# FILTER.net
KiCad netlist of a schematic drawn in Altium Designer
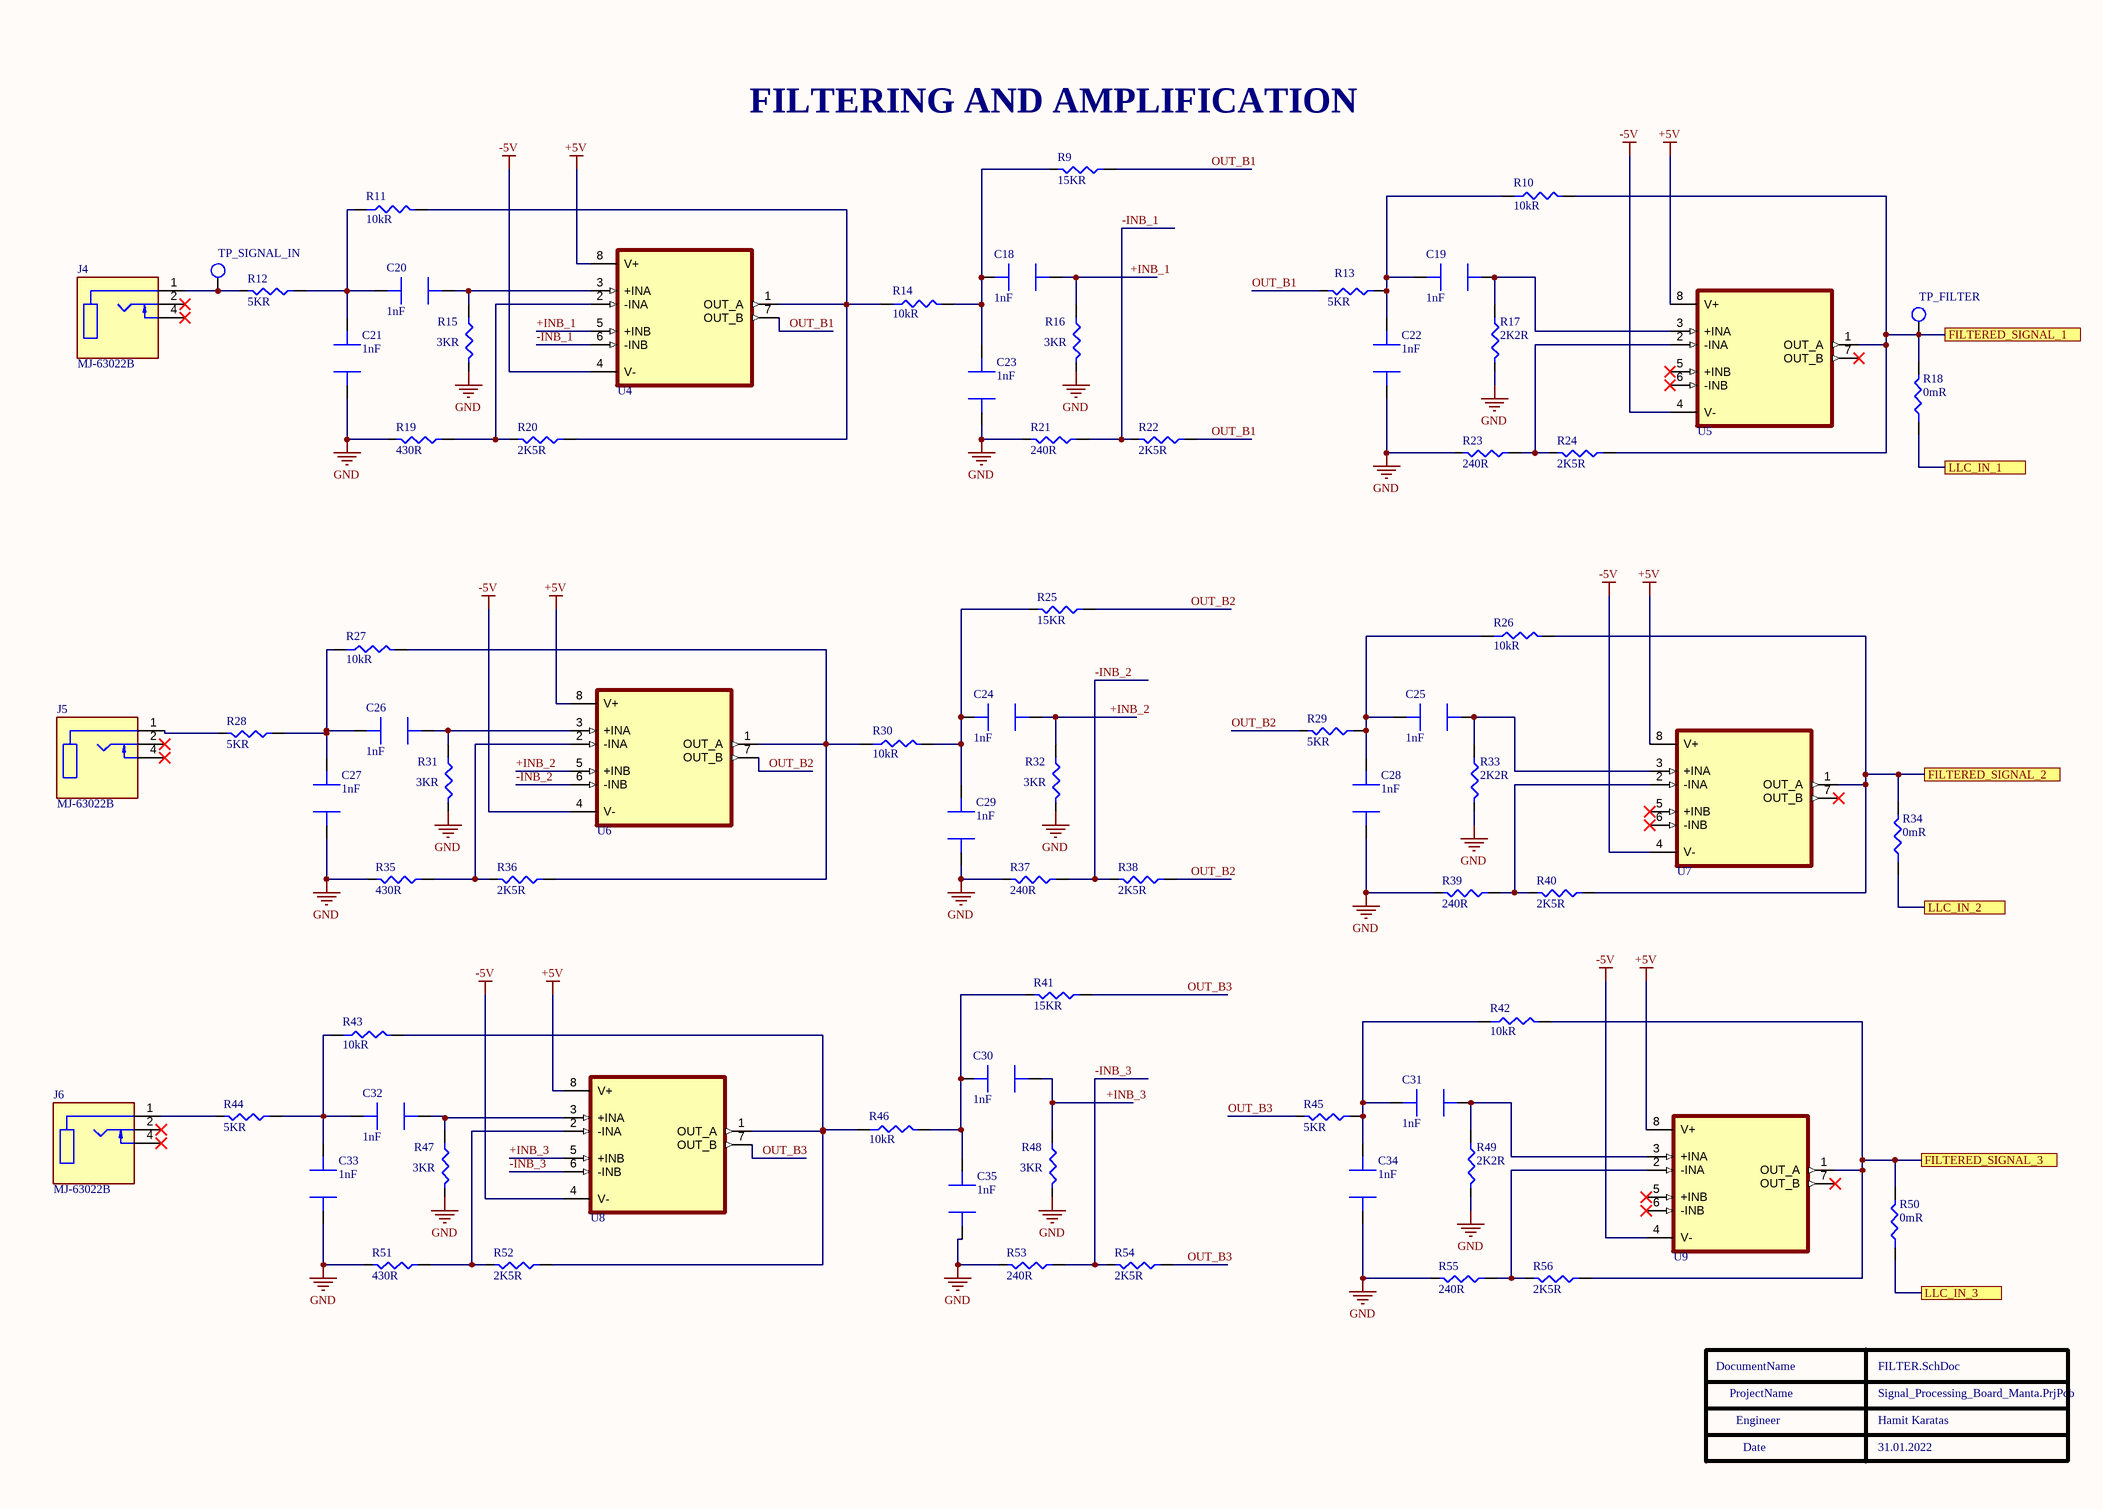
[diagram p0: FILTER.SchDoc]

(export (version "E")
  (design (tool "Eeschema 10.0.6"))
  (components
    (comp (ref "C18")
      (value "CAP CER 2.2uF")
      (footprint "CAP_1206")
      (description "Cap Ceramic 2.2uF 16V X7R 10% SMD 1206 125°C Plastic T/R")
      (fields
        (field (name "MANUFACTURER") "KEMET")
        (field (name "MANUFACTURER PART NUMBER") "C1206C225K4RACTU")
        (field (name "CAPACITANCE") "1nF")
      )
      (libsource (lib "altium_giris") (part "CAP CER 2.2uF"))
    )
    (comp (ref "C19")
      (value "CAP CER 2.2uF")
      (footprint "CAP_1206")
      (description "Cap Ceramic 2.2uF 16V X7R 10% SMD 1206 125°C Plastic T/R")
      (fields
        (field (name "MANUFACTURER") "KEMET")
        (field (name "MANUFACTURER PART NUMBER") "C1206C225K4RACTU")
        (field (name "CAPACITANCE") "1nF")
      )
      (libsource (lib "altium_giris") (part "CAP CER 2.2uF"))
    )
    (comp (ref "C20")
      (value "CAP CER 2.2uF")
      (footprint "CAP_1206")
      (description "Cap Ceramic 2.2uF 16V X7R 10% SMD 1206 125°C Plastic T/R")
      (fields
        (field (name "MANUFACTURER") "KEMET")
        (field (name "MANUFACTURER PART NUMBER") "C1206C225K4RACTU")
        (field (name "CAPACITANCE") "1nF")
      )
      (libsource (lib "altium_giris") (part "CAP CER 2.2uF"))
    )
    (comp (ref "C21")
      (value "CAP CER 2.2uF")
      (footprint "CAP_1206")
      (description "Cap Ceramic 2.2uF 16V X7R 10% SMD 1206 125°C Plastic T/R")
      (fields
        (field (name "MANUFACTURER") "KEMET")
        (field (name "MANUFACTURER PART NUMBER") "C1206C225K4RACTU")
        (field (name "CAPACITANCE") "1nF")
      )
      (libsource (lib "altium_giris") (part "CAP CER 2.2uF"))
    )
    (comp (ref "C22")
      (value "CAP CER 2.2uF")
      (footprint "CAP_1206")
      (description "Cap Ceramic 2.2uF 16V X7R 10% SMD 1206 125°C Plastic T/R")
      (fields
        (field (name "MANUFACTURER") "KEMET")
        (field (name "MANUFACTURER PART NUMBER") "C1206C225K4RACTU")
        (field (name "CAPACITANCE") "1nF")
      )
      (libsource (lib "altium_giris") (part "CAP CER 2.2uF"))
    )
    (comp (ref "C23")
      (value "CAP CER 2.2uF")
      (footprint "CAP_1206")
      (description "Cap Ceramic 2.2uF 16V X7R 10% SMD 1206 125°C Plastic T/R")
      (fields
        (field (name "MANUFACTURER") "KEMET")
        (field (name "MANUFACTURER PART NUMBER") "C1206C225K4RACTU")
        (field (name "CAPACITANCE") "1nF")
      )
      (libsource (lib "altium_giris") (part "CAP CER 2.2uF"))
    )
    (comp (ref "C24")
      (value "CAP CER 2.2uF")
      (footprint "CAP_1206")
      (description "Cap Ceramic 2.2uF 16V X7R 10% SMD 1206 125°C Plastic T/R")
      (fields
        (field (name "MANUFACTURER") "KEMET")
        (field (name "MANUFACTURER PART NUMBER") "C1206C225K4RACTU")
        (field (name "CAPACITANCE") "1nF")
      )
      (libsource (lib "altium_giris") (part "CAP CER 2.2uF"))
    )
    (comp (ref "C25")
      (value "CAP CER 2.2uF")
      (footprint "CAP_1206")
      (description "Cap Ceramic 2.2uF 16V X7R 10% SMD 1206 125°C Plastic T/R")
      (fields
        (field (name "MANUFACTURER") "KEMET")
        (field (name "MANUFACTURER PART NUMBER") "C1206C225K4RACTU")
        (field (name "CAPACITANCE") "1nF")
      )
      (libsource (lib "altium_giris") (part "CAP CER 2.2uF"))
    )
    (comp (ref "C26")
      (value "CAP CER 2.2uF")
      (footprint "CAP_1206")
      (description "Cap Ceramic 2.2uF 16V X7R 10% SMD 1206 125°C Plastic T/R")
      (fields
        (field (name "MANUFACTURER") "KEMET")
        (field (name "MANUFACTURER PART NUMBER") "C1206C225K4RACTU")
        (field (name "CAPACITANCE") "1nF")
      )
      (libsource (lib "altium_giris") (part "CAP CER 2.2uF"))
    )
    (comp (ref "C27")
      (value "CAP CER 2.2uF")
      (footprint "CAP_1206")
      (description "Cap Ceramic 2.2uF 16V X7R 10% SMD 1206 125°C Plastic T/R")
      (fields
        (field (name "MANUFACTURER") "KEMET")
        (field (name "MANUFACTURER PART NUMBER") "C1206C225K4RACTU")
        (field (name "CAPACITANCE") "1nF")
      )
      (libsource (lib "altium_giris") (part "CAP CER 2.2uF"))
    )
    (comp (ref "C28")
      (value "CAP CER 2.2uF")
      (footprint "CAP_1206")
      (description "Cap Ceramic 2.2uF 16V X7R 10% SMD 1206 125°C Plastic T/R")
      (fields
        (field (name "MANUFACTURER") "KEMET")
        (field (name "MANUFACTURER PART NUMBER") "C1206C225K4RACTU")
        (field (name "CAPACITANCE") "1nF")
      )
      (libsource (lib "altium_giris") (part "CAP CER 2.2uF"))
    )
    (comp (ref "C29")
      (value "CAP CER 2.2uF")
      (footprint "CAP_1206")
      (description "Cap Ceramic 2.2uF 16V X7R 10% SMD 1206 125°C Plastic T/R")
      (fields
        (field (name "MANUFACTURER") "KEMET")
        (field (name "MANUFACTURER PART NUMBER") "C1206C225K4RACTU")
        (field (name "CAPACITANCE") "1nF")
      )
      (libsource (lib "altium_giris") (part "CAP CER 2.2uF"))
    )
    (comp (ref "C30")
      (value "CAP CER 2.2uF")
      (footprint "CAP_1206")
      (description "Cap Ceramic 2.2uF 16V X7R 10% SMD 1206 125°C Plastic T/R")
      (fields
        (field (name "MANUFACTURER") "KEMET")
        (field (name "MANUFACTURER PART NUMBER") "C1206C225K4RACTU")
        (field (name "CAPACITANCE") "1nF")
      )
      (libsource (lib "altium_giris") (part "CAP CER 2.2uF"))
    )
    (comp (ref "C31")
      (value "CAP CER 2.2uF")
      (footprint "CAP_1206")
      (description "Cap Ceramic 2.2uF 16V X7R 10% SMD 1206 125°C Plastic T/R")
      (fields
        (field (name "MANUFACTURER") "KEMET")
        (field (name "MANUFACTURER PART NUMBER") "C1206C225K4RACTU")
        (field (name "CAPACITANCE") "1nF")
      )
      (libsource (lib "altium_giris") (part "CAP CER 2.2uF"))
    )
    (comp (ref "C32")
      (value "CAP CER 2.2uF")
      (footprint "CAP_1206")
      (description "Cap Ceramic 2.2uF 16V X7R 10% SMD 1206 125°C Plastic T/R")
      (fields
        (field (name "MANUFACTURER") "KEMET")
        (field (name "MANUFACTURER PART NUMBER") "C1206C225K4RACTU")
        (field (name "CAPACITANCE") "1nF")
      )
      (libsource (lib "altium_giris") (part "CAP CER 2.2uF"))
    )
    (comp (ref "C33")
      (value "CAP CER 2.2uF")
      (footprint "CAP_1206")
      (description "Cap Ceramic 2.2uF 16V X7R 10% SMD 1206 125°C Plastic T/R")
      (fields
        (field (name "MANUFACTURER") "KEMET")
        (field (name "MANUFACTURER PART NUMBER") "C1206C225K4RACTU")
        (field (name "CAPACITANCE") "1nF")
      )
      (libsource (lib "altium_giris") (part "CAP CER 2.2uF"))
    )
    (comp (ref "C34")
      (value "CAP CER 2.2uF")
      (footprint "CAP_1206")
      (description "Cap Ceramic 2.2uF 16V X7R 10% SMD 1206 125°C Plastic T/R")
      (fields
        (field (name "MANUFACTURER") "KEMET")
        (field (name "MANUFACTURER PART NUMBER") "C1206C225K4RACTU")
        (field (name "CAPACITANCE") "1nF")
      )
      (libsource (lib "altium_giris") (part "CAP CER 2.2uF"))
    )
    (comp (ref "C35")
      (value "CAP CER 2.2uF")
      (footprint "CAP_1206")
      (description "Cap Ceramic 2.2uF 16V X7R 10% SMD 1206 125°C Plastic T/R")
      (fields
        (field (name "MANUFACTURER") "KEMET")
        (field (name "MANUFACTURER PART NUMBER") "C1206C225K4RACTU")
        (field (name "CAPACITANCE") "1nF")
      )
      (libsource (lib "altium_giris") (part "CAP CER 2.2uF"))
    )
    (comp (ref "J4")
      (value "MJ-63022B")
      (footprint "JACK FEMALE 6.3")
      (description "Conn Audio Jack F 2 POS Solder RA Thru-Hole 3 Terminal 1 Port Bulk")
      (fields (field (name "MANUFACTURER") "CUI Devices"))
      (libsource (lib "altium_giris") (part "MJ-63022B"))
    )
    (comp (ref "J5")
      (value "MJ-63022B")
      (footprint "JACK FEMALE 6.3")
      (description "Conn Audio Jack F 2 POS Solder RA Thru-Hole 3 Terminal 1 Port Bulk")
      (fields (field (name "MANUFACTURER") "CUI Devices"))
      (libsource (lib "altium_giris") (part "MJ-63022B"))
    )
    (comp (ref "J6")
      (value "MJ-63022B")
      (footprint "JACK FEMALE 6.3")
      (description "Conn Audio Jack F 2 POS Solder RA Thru-Hole 3 Terminal 1 Port Bulk")
      (fields (field (name "MANUFACTURER") "CUI Devices"))
      (libsource (lib "altium_giris") (part "MJ-63022B"))
    )
    (comp (ref "R9")
      (value "RC0603FR-0710KL")
      (footprint "RES_0603")
      (description "RES 1K %1 OHM 0603 SMD")
      (fields
        (field (name "MANUFACTURER") "Yageo")
        (field (name "MANUFACTURER PART NUMBER") "RC0603JR-071KL")
        (field (name "RESISTANCE") "15KR")
        (field (name "DESIGNED BY") "Hamit")
      )
      (libsource (lib "altium_giris") (part "RES 1K OHM 0603"))
    )
    (comp (ref "R10")
      (value "RES 10K OHM 0603")
      (footprint "RES_0603")
      (description "Res General Purpose Thick Film 0603 10K Ohm 1% 1/10W ±100ppm/°C Molded SMD Paper T/R")
      (fields
        (field (name "MANUFACTURER") "Yageo")
        (field (name "MANUFACTURER PART NUMBER") "RC0603FR-0710KL")
        (field (name "RESISTANCE") "10kR")
        (field (name "DESIGNED BY") "Hamit")
      )
      (libsource (lib "altium_giris") (part "RES 10K OHM 0603"))
    )
    (comp (ref "R11")
      (value "RES 10K OHM 0603")
      (footprint "RES_0603")
      (description "Res General Purpose Thick Film 0603 10K Ohm 1% 1/10W ±100ppm/°C Molded SMD Paper T/R")
      (fields
        (field (name "MANUFACTURER") "Yageo")
        (field (name "MANUFACTURER PART NUMBER") "RC0603FR-0710KL")
        (field (name "RESISTANCE") "10kR")
        (field (name "DESIGNED BY") "Hamit")
      )
      (libsource (lib "altium_giris") (part "RES 10K OHM 0603"))
    )
    (comp (ref "R12")
      (value "RC0603FR-0710KL")
      (footprint "RES_0603")
      (description "RES 1K %1 OHM 0603 SMD")
      (fields
        (field (name "MANUFACTURER") "Yageo")
        (field (name "MANUFACTURER PART NUMBER") "RC0603JR-071KL")
        (field (name "RESISTANCE") "5KR")
        (field (name "DESIGNED BY") "Hamit")
      )
      (libsource (lib "altium_giris") (part "RES 1K OHM 0603"))
    )
    (comp (ref "R13")
      (value "RC0603FR-0710KL")
      (footprint "RES_0603")
      (description "RES 1K %1 OHM 0603 SMD")
      (fields
        (field (name "MANUFACTURER") "Yageo")
        (field (name "MANUFACTURER PART NUMBER") "RC0603JR-071KL")
        (field (name "RESISTANCE") "5KR")
        (field (name "DESIGNED BY") "Hamit")
      )
      (libsource (lib "altium_giris") (part "RES 1K OHM 0603"))
    )
    (comp (ref "R14")
      (value "RES 10K OHM 0603")
      (footprint "RES_0603")
      (description "Res General Purpose Thick Film 0603 10K Ohm 1% 1/10W ±100ppm/°C Molded SMD Paper T/R")
      (fields
        (field (name "MANUFACTURER") "Yageo")
        (field (name "MANUFACTURER PART NUMBER") "RC0603FR-0710KL")
        (field (name "RESISTANCE") "10kR")
        (field (name "DESIGNED BY") "Hamit")
      )
      (libsource (lib "altium_giris") (part "RES 10K OHM 0603"))
    )
    (comp (ref "R15")
      (value "430R")
      (footprint "RES 0805")
      (description "Res Thick Film 0805 430 Ohm 1% 1/8W ±100ppm/°C Molded SMD SMD Paper T/R")
      (fields
        (field (name "MANUFACTURER") "Stackpole Electronics")
        (field (name "MANUFACTURER PART NUMBER") "RMCF0805FT430R")
        (field (name "RESISTANCE") "3KR")
      )
      (libsource (lib "altium_giris") (part "RES 430 OHM 0805"))
    )
    (comp (ref "R16")
      (value "430R")
      (footprint "RES 0805")
      (description "Res Thick Film 0805 430 Ohm 1% 1/8W ±100ppm/°C Molded SMD SMD Paper T/R")
      (fields
        (field (name "MANUFACTURER") "Stackpole Electronics")
        (field (name "MANUFACTURER PART NUMBER") "RMCF0805FT430R")
        (field (name "RESISTANCE") "3KR")
      )
      (libsource (lib "altium_giris") (part "RES 430 OHM 0805"))
    )
    (comp (ref "R17")
      (value "RC0603FR-0710KL")
      (footprint "RES_0603")
      (description "RES 1K %1 OHM 0603 SMD")
      (fields
        (field (name "MANUFACTURER") "Yageo")
        (field (name "MANUFACTURER PART NUMBER") "RC0603JR-071KL")
        (field (name "RESISTANCE") "2K2R")
        (field (name "DESIGNED BY") "Hamit")
      )
      (libsource (lib "altium_giris") (part "RES 1K OHM 0603"))
    )
    (comp (ref "R18")
      (value "RC0603JR-070RL")
      (footprint "RES_0603")
      (description "RES SMD 0 OHM JUMPER 1/10W 0603")
      (fields
        (field (name "MANUFACTURER") "Yageo")
        (field (name "TOLERANCE") "1%")
        (field (name "RESISTANCE") "0mR")
        (field (name "DESIGNED BY") "Hamit")
      )
      (libsource (lib "altium_giris") (part "RES 0 ohm 0603"))
    )
    (comp (ref "R19")
      (value "430R")
      (footprint "RES 0805")
      (description "Res Thick Film 0805 430 Ohm 1% 1/8W ±100ppm/°C Molded SMD SMD Paper T/R")
      (fields
        (field (name "MANUFACTURER") "Stackpole Electronics")
        (field (name "MANUFACTURER PART NUMBER") "RMCF0805FT430R")
        (field (name "RESISTANCE") "430R")
      )
      (libsource (lib "altium_giris") (part "RES 430 OHM 0805"))
    )
    (comp (ref "R20")
      (value "RC0603FR-0710KL")
      (footprint "RES_0603")
      (description "RES 1K %1 OHM 0603 SMD")
      (fields
        (field (name "MANUFACTURER") "Yageo")
        (field (name "MANUFACTURER PART NUMBER") "RC0603JR-071KL")
        (field (name "RESISTANCE") "2K5R")
        (field (name "DESIGNED BY") "Hamit")
      )
      (libsource (lib "altium_giris") (part "RES 1K OHM 0603"))
    )
    (comp (ref "R21")
      (value "430R")
      (footprint "RES 0805")
      (description "Res Thick Film 0805 430 Ohm 1% 1/8W ±100ppm/°C Molded SMD SMD Paper T/R")
      (fields
        (field (name "MANUFACTURER") "Stackpole Electronics")
        (field (name "MANUFACTURER PART NUMBER") "RMCF0805FT430R")
        (field (name "RESISTANCE") "240R")
      )
      (libsource (lib "altium_giris") (part "RES 430 OHM 0805"))
    )
    (comp (ref "R22")
      (value "RC0603FR-0710KL")
      (footprint "RES_0603")
      (description "RES 1K %1 OHM 0603 SMD")
      (fields
        (field (name "MANUFACTURER") "Yageo")
        (field (name "MANUFACTURER PART NUMBER") "RC0603JR-071KL")
        (field (name "RESISTANCE") "2K5R")
        (field (name "DESIGNED BY") "Hamit")
      )
      (libsource (lib "altium_giris") (part "RES 1K OHM 0603"))
    )
    (comp (ref "R23")
      (value "430R")
      (footprint "RES 0805")
      (description "Res Thick Film 0805 430 Ohm 1% 1/8W ±100ppm/°C Molded SMD SMD Paper T/R")
      (fields
        (field (name "MANUFACTURER") "Stackpole Electronics")
        (field (name "MANUFACTURER PART NUMBER") "RMCF0805FT430R")
        (field (name "RESISTANCE") "240R")
      )
      (libsource (lib "altium_giris") (part "RES 430 OHM 0805"))
    )
    (comp (ref "R24")
      (value "RC0603FR-0710KL")
      (footprint "RES_0603")
      (description "RES 1K %1 OHM 0603 SMD")
      (fields
        (field (name "MANUFACTURER") "Yageo")
        (field (name "MANUFACTURER PART NUMBER") "RC0603JR-071KL")
        (field (name "RESISTANCE") "2K5R")
        (field (name "DESIGNED BY") "Hamit")
      )
      (libsource (lib "altium_giris") (part "RES 1K OHM 0603"))
    )
    (comp (ref "R25")
      (value "RC0603FR-0710KL")
      (footprint "RES_0603")
      (description "RES 1K %1 OHM 0603 SMD")
      (fields
        (field (name "MANUFACTURER") "Yageo")
        (field (name "MANUFACTURER PART NUMBER") "RC0603JR-071KL")
        (field (name "RESISTANCE") "15KR")
        (field (name "DESIGNED BY") "Hamit")
      )
      (libsource (lib "altium_giris") (part "RES 1K OHM 0603"))
    )
    (comp (ref "R26")
      (value "RES 10K OHM 0603")
      (footprint "RES_0603")
      (description "Res General Purpose Thick Film 0603 10K Ohm 1% 1/10W ±100ppm/°C Molded SMD Paper T/R")
      (fields
        (field (name "MANUFACTURER") "Yageo")
        (field (name "MANUFACTURER PART NUMBER") "RC0603FR-0710KL")
        (field (name "RESISTANCE") "10kR")
        (field (name "DESIGNED BY") "Hamit")
      )
      (libsource (lib "altium_giris") (part "RES 10K OHM 0603"))
    )
    (comp (ref "R27")
      (value "RES 10K OHM 0603")
      (footprint "RES_0603")
      (description "Res General Purpose Thick Film 0603 10K Ohm 1% 1/10W ±100ppm/°C Molded SMD Paper T/R")
      (fields
        (field (name "MANUFACTURER") "Yageo")
        (field (name "MANUFACTURER PART NUMBER") "RC0603FR-0710KL")
        (field (name "RESISTANCE") "10kR")
        (field (name "DESIGNED BY") "Hamit")
      )
      (libsource (lib "altium_giris") (part "RES 10K OHM 0603"))
    )
    (comp (ref "R28")
      (value "RC0603FR-0710KL")
      (footprint "RES_0603")
      (description "RES 1K %1 OHM 0603 SMD")
      (fields
        (field (name "MANUFACTURER") "Yageo")
        (field (name "MANUFACTURER PART NUMBER") "RC0603JR-071KL")
        (field (name "RESISTANCE") "5KR")
        (field (name "DESIGNED BY") "Hamit")
      )
      (libsource (lib "altium_giris") (part "RES 1K OHM 0603"))
    )
    (comp (ref "R29")
      (value "RC0603FR-0710KL")
      (footprint "RES_0603")
      (description "RES 1K %1 OHM 0603 SMD")
      (fields
        (field (name "MANUFACTURER") "Yageo")
        (field (name "MANUFACTURER PART NUMBER") "RC0603JR-071KL")
        (field (name "RESISTANCE") "5KR")
        (field (name "DESIGNED BY") "Hamit")
      )
      (libsource (lib "altium_giris") (part "RES 1K OHM 0603"))
    )
    (comp (ref "R30")
      (value "RES 10K OHM 0603")
      (footprint "RES_0603")
      (description "Res General Purpose Thick Film 0603 10K Ohm 1% 1/10W ±100ppm/°C Molded SMD Paper T/R")
      (fields
        (field (name "MANUFACTURER") "Yageo")
        (field (name "MANUFACTURER PART NUMBER") "RC0603FR-0710KL")
        (field (name "RESISTANCE") "10kR")
        (field (name "DESIGNED BY") "Hamit")
      )
      (libsource (lib "altium_giris") (part "RES 10K OHM 0603"))
    )
    (comp (ref "R31")
      (value "430R")
      (footprint "RES 0805")
      (description "Res Thick Film 0805 430 Ohm 1% 1/8W ±100ppm/°C Molded SMD SMD Paper T/R")
      (fields
        (field (name "MANUFACTURER") "Stackpole Electronics")
        (field (name "MANUFACTURER PART NUMBER") "RMCF0805FT430R")
        (field (name "RESISTANCE") "3KR")
      )
      (libsource (lib "altium_giris") (part "RES 430 OHM 0805"))
    )
    (comp (ref "R32")
      (value "430R")
      (footprint "RES 0805")
      (description "Res Thick Film 0805 430 Ohm 1% 1/8W ±100ppm/°C Molded SMD SMD Paper T/R")
      (fields
        (field (name "MANUFACTURER") "Stackpole Electronics")
        (field (name "MANUFACTURER PART NUMBER") "RMCF0805FT430R")
        (field (name "RESISTANCE") "3KR")
      )
      (libsource (lib "altium_giris") (part "RES 430 OHM 0805"))
    )
    (comp (ref "R33")
      (value "RC0603FR-0710KL")
      (footprint "RES_0603")
      (description "RES 1K %1 OHM 0603 SMD")
      (fields
        (field (name "MANUFACTURER") "Yageo")
        (field (name "MANUFACTURER PART NUMBER") "RC0603JR-071KL")
        (field (name "RESISTANCE") "2K2R")
        (field (name "DESIGNED BY") "Hamit")
      )
      (libsource (lib "altium_giris") (part "RES 1K OHM 0603"))
    )
    (comp (ref "R34")
      (value "RC0603JR-070RL")
      (footprint "RES_0603")
      (description "RES SMD 0 OHM JUMPER 1/10W 0603")
      (fields
        (field (name "MANUFACTURER") "Yageo")
        (field (name "TOLERANCE") "1%")
        (field (name "RESISTANCE") "0mR")
        (field (name "DESIGNED BY") "Hamit")
      )
      (libsource (lib "altium_giris") (part "RES 0 ohm 0603"))
    )
    (comp (ref "R35")
      (value "430R")
      (footprint "RES 0805")
      (description "Res Thick Film 0805 430 Ohm 1% 1/8W ±100ppm/°C Molded SMD SMD Paper T/R")
      (fields
        (field (name "MANUFACTURER") "Stackpole Electronics")
        (field (name "MANUFACTURER PART NUMBER") "RMCF0805FT430R")
        (field (name "RESISTANCE") "430R")
      )
      (libsource (lib "altium_giris") (part "RES 430 OHM 0805"))
    )
    (comp (ref "R36")
      (value "RC0603FR-0710KL")
      (footprint "RES_0603")
      (description "RES 1K %1 OHM 0603 SMD")
      (fields
        (field (name "MANUFACTURER") "Yageo")
        (field (name "MANUFACTURER PART NUMBER") "RC0603JR-071KL")
        (field (name "RESISTANCE") "2K5R")
        (field (name "DESIGNED BY") "Hamit")
      )
      (libsource (lib "altium_giris") (part "RES 1K OHM 0603"))
    )
    (comp (ref "R37")
      (value "430R")
      (footprint "RES 0805")
      (description "Res Thick Film 0805 430 Ohm 1% 1/8W ±100ppm/°C Molded SMD SMD Paper T/R")
      (fields
        (field (name "MANUFACTURER") "Stackpole Electronics")
        (field (name "MANUFACTURER PART NUMBER") "RMCF0805FT430R")
        (field (name "RESISTANCE") "240R")
      )
      (libsource (lib "altium_giris") (part "RES 430 OHM 0805"))
    )
    (comp (ref "R38")
      (value "RC0603FR-0710KL")
      (footprint "RES_0603")
      (description "RES 1K %1 OHM 0603 SMD")
      (fields
        (field (name "MANUFACTURER") "Yageo")
        (field (name "MANUFACTURER PART NUMBER") "RC0603JR-071KL")
        (field (name "RESISTANCE") "2K5R")
        (field (name "DESIGNED BY") "Hamit")
      )
      (libsource (lib "altium_giris") (part "RES 1K OHM 0603"))
    )
    (comp (ref "R39")
      (value "430R")
      (footprint "RES 0805")
      (description "Res Thick Film 0805 430 Ohm 1% 1/8W ±100ppm/°C Molded SMD SMD Paper T/R")
      (fields
        (field (name "MANUFACTURER") "Stackpole Electronics")
        (field (name "MANUFACTURER PART NUMBER") "RMCF0805FT430R")
        (field (name "RESISTANCE") "240R")
      )
      (libsource (lib "altium_giris") (part "RES 430 OHM 0805"))
    )
    (comp (ref "R40")
      (value "RC0603FR-0710KL")
      (footprint "RES_0603")
      (description "RES 1K %1 OHM 0603 SMD")
      (fields
        (field (name "MANUFACTURER") "Yageo")
        (field (name "MANUFACTURER PART NUMBER") "RC0603JR-071KL")
        (field (name "RESISTANCE") "2K5R")
        (field (name "DESIGNED BY") "Hamit")
      )
      (libsource (lib "altium_giris") (part "RES 1K OHM 0603"))
    )
    (comp (ref "R41")
      (value "RC0603FR-0710KL")
      (footprint "RES_0603")
      (description "RES 1K %1 OHM 0603 SMD")
      (fields
        (field (name "MANUFACTURER") "Yageo")
        (field (name "MANUFACTURER PART NUMBER") "RC0603JR-071KL")
        (field (name "RESISTANCE") "15KR")
        (field (name "DESIGNED BY") "Hamit")
      )
      (libsource (lib "altium_giris") (part "RES 1K OHM 0603"))
    )
    (comp (ref "R42")
      (value "RES 10K OHM 0603")
      (footprint "RES_0603")
      (description "Res General Purpose Thick Film 0603 10K Ohm 1% 1/10W ±100ppm/°C Molded SMD Paper T/R")
      (fields
        (field (name "MANUFACTURER") "Yageo")
        (field (name "MANUFACTURER PART NUMBER") "RC0603FR-0710KL")
        (field (name "RESISTANCE") "10kR")
        (field (name "DESIGNED BY") "Hamit")
      )
      (libsource (lib "altium_giris") (part "RES 10K OHM 0603"))
    )
    (comp (ref "R43")
      (value "RES 10K OHM 0603")
      (footprint "RES_0603")
      (description "Res General Purpose Thick Film 0603 10K Ohm 1% 1/10W ±100ppm/°C Molded SMD Paper T/R")
      (fields
        (field (name "MANUFACTURER") "Yageo")
        (field (name "MANUFACTURER PART NUMBER") "RC0603FR-0710KL")
        (field (name "RESISTANCE") "10kR")
        (field (name "DESIGNED BY") "Hamit")
      )
      (libsource (lib "altium_giris") (part "RES 10K OHM 0603"))
    )
    (comp (ref "R44")
      (value "RC0603FR-0710KL")
      (footprint "RES_0603")
      (description "RES 1K %1 OHM 0603 SMD")
      (fields
        (field (name "MANUFACTURER") "Yageo")
        (field (name "MANUFACTURER PART NUMBER") "RC0603JR-071KL")
        (field (name "RESISTANCE") "5KR")
        (field (name "DESIGNED BY") "Hamit")
      )
      (libsource (lib "altium_giris") (part "RES 1K OHM 0603"))
    )
    (comp (ref "R45")
      (value "RC0603FR-0710KL")
      (footprint "RES_0603")
      (description "RES 1K %1 OHM 0603 SMD")
      (fields
        (field (name "MANUFACTURER") "Yageo")
        (field (name "MANUFACTURER PART NUMBER") "RC0603JR-071KL")
        (field (name "RESISTANCE") "5KR")
        (field (name "DESIGNED BY") "Hamit")
      )
      (libsource (lib "altium_giris") (part "RES 1K OHM 0603"))
    )
    (comp (ref "R46")
      (value "RES 10K OHM 0603")
      (footprint "RES_0603")
      (description "Res General Purpose Thick Film 0603 10K Ohm 1% 1/10W ±100ppm/°C Molded SMD Paper T/R")
      (fields
        (field (name "MANUFACTURER") "Yageo")
        (field (name "MANUFACTURER PART NUMBER") "RC0603FR-0710KL")
        (field (name "RESISTANCE") "10kR")
        (field (name "DESIGNED BY") "Hamit")
      )
      (libsource (lib "altium_giris") (part "RES 10K OHM 0603"))
    )
    (comp (ref "R47")
      (value "430R")
      (footprint "RES 0805")
      (description "Res Thick Film 0805 430 Ohm 1% 1/8W ±100ppm/°C Molded SMD SMD Paper T/R")
      (fields
        (field (name "MANUFACTURER") "Stackpole Electronics")
        (field (name "MANUFACTURER PART NUMBER") "RMCF0805FT430R")
        (field (name "RESISTANCE") "3KR")
      )
      (libsource (lib "altium_giris") (part "RES 430 OHM 0805"))
    )
    (comp (ref "R48")
      (value "430R")
      (footprint "RES 0805")
      (description "Res Thick Film 0805 430 Ohm 1% 1/8W ±100ppm/°C Molded SMD SMD Paper T/R")
      (fields
        (field (name "MANUFACTURER") "Stackpole Electronics")
        (field (name "MANUFACTURER PART NUMBER") "RMCF0805FT430R")
        (field (name "RESISTANCE") "3KR")
      )
      (libsource (lib "altium_giris") (part "RES 430 OHM 0805"))
    )
    (comp (ref "R49")
      (value "RC0603FR-0710KL")
      (footprint "RES_0603")
      (description "RES 1K %1 OHM 0603 SMD")
      (fields
        (field (name "MANUFACTURER") "Yageo")
        (field (name "MANUFACTURER PART NUMBER") "RC0603JR-071KL")
        (field (name "RESISTANCE") "2K2R")
        (field (name "DESIGNED BY") "Hamit")
      )
      (libsource (lib "altium_giris") (part "RES 1K OHM 0603"))
    )
    (comp (ref "R50")
      (value "RC0603JR-070RL")
      (footprint "RES_0603")
      (description "RES SMD 0 OHM JUMPER 1/10W 0603")
      (fields
        (field (name "MANUFACTURER") "Yageo")
        (field (name "TOLERANCE") "1%")
        (field (name "RESISTANCE") "0mR")
        (field (name "DESIGNED BY") "Hamit")
      )
      (libsource (lib "altium_giris") (part "RES 0 ohm 0603"))
    )
    (comp (ref "R51")
      (value "430R")
      (footprint "RES 0805")
      (description "Res Thick Film 0805 430 Ohm 1% 1/8W ±100ppm/°C Molded SMD SMD Paper T/R")
      (fields
        (field (name "MANUFACTURER") "Stackpole Electronics")
        (field (name "MANUFACTURER PART NUMBER") "RMCF0805FT430R")
        (field (name "RESISTANCE") "430R")
      )
      (libsource (lib "altium_giris") (part "RES 430 OHM 0805"))
    )
    (comp (ref "R52")
      (value "RC0603FR-0710KL")
      (footprint "RES_0603")
      (description "RES 1K %1 OHM 0603 SMD")
      (fields
        (field (name "MANUFACTURER") "Yageo")
        (field (name "MANUFACTURER PART NUMBER") "RC0603JR-071KL")
        (field (name "RESISTANCE") "2K5R")
        (field (name "DESIGNED BY") "Hamit")
      )
      (libsource (lib "altium_giris") (part "RES 1K OHM 0603"))
    )
    (comp (ref "R53")
      (value "430R")
      (footprint "RES 0805")
      (description "Res Thick Film 0805 430 Ohm 1% 1/8W ±100ppm/°C Molded SMD SMD Paper T/R")
      (fields
        (field (name "MANUFACTURER") "Stackpole Electronics")
        (field (name "MANUFACTURER PART NUMBER") "RMCF0805FT430R")
        (field (name "RESISTANCE") "240R")
      )
      (libsource (lib "altium_giris") (part "RES 430 OHM 0805"))
    )
    (comp (ref "R54")
      (value "RC0603FR-0710KL")
      (footprint "RES_0603")
      (description "RES 1K %1 OHM 0603 SMD")
      (fields
        (field (name "MANUFACTURER") "Yageo")
        (field (name "MANUFACTURER PART NUMBER") "RC0603JR-071KL")
        (field (name "RESISTANCE") "2K5R")
        (field (name "DESIGNED BY") "Hamit")
      )
      (libsource (lib "altium_giris") (part "RES 1K OHM 0603"))
    )
    (comp (ref "R55")
      (value "430R")
      (footprint "RES 0805")
      (description "Res Thick Film 0805 430 Ohm 1% 1/8W ±100ppm/°C Molded SMD SMD Paper T/R")
      (fields
        (field (name "MANUFACTURER") "Stackpole Electronics")
        (field (name "MANUFACTURER PART NUMBER") "RMCF0805FT430R")
        (field (name "RESISTANCE") "240R")
      )
      (libsource (lib "altium_giris") (part "RES 430 OHM 0805"))
    )
    (comp (ref "R56")
      (value "RC0603FR-0710KL")
      (footprint "RES_0603")
      (description "RES 1K %1 OHM 0603 SMD")
      (fields
        (field (name "MANUFACTURER") "Yageo")
        (field (name "MANUFACTURER PART NUMBER") "RC0603JR-071KL")
        (field (name "RESISTANCE") "2K5R")
        (field (name "DESIGNED BY") "Hamit")
      )
      (libsource (lib "altium_giris") (part "RES 1K OHM 0603"))
    )
    (comp (ref "TP_FILTER")
      (value "TEST_POINT")
      (footprint "TEST POINT")
      (libsource (lib "altium_giris") (part "TEST POINT"))
    )
    (comp (ref "TP_SIGNAL_IN")
      (value "TEST_POINT")
      (footprint "TEST POINT")
      (libsource (lib "altium_giris") (part "TEST POINT"))
    )
    (comp (ref "U4")
      (value "Opamp lmh6612")
      (footprint "SOIC-8")
      (description "Single Supply, Dual 345 MHz Rail-to-Rail Output Amplifier and PLC Line Driver 8-SOIC -40 to 125")
      (fields
        (field (name "MANUFACTURER") "TI National Semiconductor")
        (field (name "MANUFACTURER PART NUMBER") "LMH6612MAX/NOPB")
      )
      (libsource (lib "altium_giris") (part "Opamp lmh6612"))
    )
    (comp (ref "U5")
      (value "Opamp lmh6612")
      (footprint "SOIC-8")
      (description "Single Supply, Dual 345 MHz Rail-to-Rail Output Amplifier and PLC Line Driver 8-SOIC -40 to 125")
      (fields
        (field (name "MANUFACTURER") "TI National Semiconductor")
        (field (name "MANUFACTURER PART NUMBER") "LMH6612MAX/NOPB")
      )
      (libsource (lib "altium_giris") (part "Opamp lmh6612"))
    )
    (comp (ref "U6")
      (value "Opamp lmh6612")
      (footprint "SOIC-8")
      (description "Single Supply, Dual 345 MHz Rail-to-Rail Output Amplifier and PLC Line Driver 8-SOIC -40 to 125")
      (fields
        (field (name "MANUFACTURER") "TI National Semiconductor")
        (field (name "MANUFACTURER PART NUMBER") "LMH6612MAX/NOPB")
      )
      (libsource (lib "altium_giris") (part "Opamp lmh6612"))
    )
    (comp (ref "U7")
      (value "Opamp lmh6612")
      (footprint "SOIC-8")
      (description "Single Supply, Dual 345 MHz Rail-to-Rail Output Amplifier and PLC Line Driver 8-SOIC -40 to 125")
      (fields
        (field (name "MANUFACTURER") "TI National Semiconductor")
        (field (name "MANUFACTURER PART NUMBER") "LMH6612MAX/NOPB")
      )
      (libsource (lib "altium_giris") (part "Opamp lmh6612"))
    )
    (comp (ref "U8")
      (value "Opamp lmh6612")
      (footprint "SOIC-8")
      (description "Single Supply, Dual 345 MHz Rail-to-Rail Output Amplifier and PLC Line Driver 8-SOIC -40 to 125")
      (fields
        (field (name "MANUFACTURER") "TI National Semiconductor")
        (field (name "MANUFACTURER PART NUMBER") "LMH6612MAX/NOPB")
      )
      (libsource (lib "altium_giris") (part "Opamp lmh6612"))
    )
    (comp (ref "U9")
      (value "Opamp lmh6612")
      (footprint "SOIC-8")
      (description "Single Supply, Dual 345 MHz Rail-to-Rail Output Amplifier and PLC Line Driver 8-SOIC -40 to 125")
      (fields
        (field (name "MANUFACTURER") "TI National Semiconductor")
        (field (name "MANUFACTURER PART NUMBER") "LMH6612MAX/NOPB")
      )
      (libsource (lib "altium_giris") (part "Opamp lmh6612"))
    )
  )
  (nets
    (net (code "1") (name "+5V") (class "Default")
      (node (ref "U4") (pin "8") (pinfunction "V+_8") (pintype "power_in"))
      (node (ref "U5") (pin "8") (pinfunction "V+_8") (pintype "power_in"))
      (node (ref "U6") (pin "8") (pinfunction "V+_8") (pintype "power_in"))
      (node (ref "U7") (pin "8") (pinfunction "V+_8") (pintype "power_in"))
      (node (ref "U8") (pin "8") (pinfunction "V+_8") (pintype "power_in"))
      (node (ref "U9") (pin "8") (pinfunction "V+_8") (pintype "power_in"))
    )
    (net (code "2") (name "-5V") (class "Default")
      (node (ref "U4") (pin "4") (pinfunction "V-_4") (pintype "power_in"))
      (node (ref "U5") (pin "4") (pinfunction "V-_4") (pintype "power_in"))
      (node (ref "U6") (pin "4") (pinfunction "V-_4") (pintype "power_in"))
      (node (ref "U7") (pin "4") (pinfunction "V-_4") (pintype "power_in"))
      (node (ref "U8") (pin "4") (pinfunction "V-_4") (pintype "power_in"))
      (node (ref "U9") (pin "4") (pinfunction "V-_4") (pintype "power_in"))
    )
    (net (code "3") (name "/+INB_1") (class "Default")
      (node (ref "C18") (pin "2") (pinfunction "2_2") (pintype "passive"))
      (node (ref "R16") (pin "2") (pinfunction "2_2") (pintype "passive"))
      (node (ref "U4") (pin "5") (pinfunction "+INB_5") (pintype "input"))
    )
    (net (code "4") (name "/+INB_2") (class "Default")
      (node (ref "C24") (pin "2") (pinfunction "2_2") (pintype "passive"))
      (node (ref "R32") (pin "2") (pinfunction "2_2") (pintype "passive"))
      (node (ref "U6") (pin "5") (pinfunction "+INB_5") (pintype "input"))
    )
    (net (code "5") (name "/+INB_3") (class "Default")
      (node (ref "C30") (pin "2") (pinfunction "2_2") (pintype "passive"))
      (node (ref "R48") (pin "2") (pinfunction "2_2") (pintype "passive"))
      (node (ref "U8") (pin "5") (pinfunction "+INB_5") (pintype "input"))
    )
    (net (code "6") (name "/-INB_1") (class "Default")
      (node (ref "R21") (pin "2") (pinfunction "2_2") (pintype "passive"))
      (node (ref "R22") (pin "1") (pinfunction "1_1") (pintype "passive"))
      (node (ref "U4") (pin "6") (pinfunction "-INB_6") (pintype "input"))
    )
    (net (code "7") (name "/-INB_2") (class "Default")
      (node (ref "R37") (pin "2") (pinfunction "2_2") (pintype "passive"))
      (node (ref "R38") (pin "1") (pinfunction "1_1") (pintype "passive"))
      (node (ref "U6") (pin "6") (pinfunction "-INB_6") (pintype "input"))
    )
    (net (code "8") (name "/-INB_3") (class "Default")
      (node (ref "R53") (pin "2") (pinfunction "2_2") (pintype "passive"))
      (node (ref "R54") (pin "1") (pinfunction "1_1") (pintype "passive"))
      (node (ref "U8") (pin "6") (pinfunction "-INB_6") (pintype "input"))
    )
    (net (code "9") (name "/FILTERED_SIGNAL_1") (class "Default")
      (node (ref "R10") (pin "2") (pinfunction "2_2") (pintype "passive"))
      (node (ref "R18") (pin "2") (pinfunction "2_2") (pintype "passive"))
      (node (ref "R24") (pin "2") (pinfunction "2_2") (pintype "passive"))
      (node (ref "TP_FILTER") (pin "1") (pinfunction "TP_1") (pintype "passive"))
      (node (ref "U5") (pin "1") (pinfunction "OUT_A_1") (pintype "output"))
    )
    (net (code "10") (name "/FILTERED_SIGNAL_2") (class "Default")
      (node (ref "R26") (pin "2") (pinfunction "2_2") (pintype "passive"))
      (node (ref "R34") (pin "2") (pinfunction "2_2") (pintype "passive"))
      (node (ref "R40") (pin "2") (pinfunction "2_2") (pintype "passive"))
      (node (ref "U7") (pin "1") (pinfunction "OUT_A_1") (pintype "output"))
    )
    (net (code "11") (name "/FILTERED_SIGNAL_3") (class "Default")
      (node (ref "R42") (pin "2") (pinfunction "2_2") (pintype "passive"))
      (node (ref "R50") (pin "2") (pinfunction "2_2") (pintype "passive"))
      (node (ref "R56") (pin "2") (pinfunction "2_2") (pintype "passive"))
      (node (ref "U9") (pin "1") (pinfunction "OUT_A_1") (pintype "output"))
    )
    (net (code "12") (name "/LLC_IN_1") (class "Default")
      (node (ref "R18") (pin "1") (pinfunction "1_1") (pintype "passive"))
    )
    (net (code "13") (name "/LLC_IN_2") (class "Default")
      (node (ref "R34") (pin "1") (pinfunction "1_1") (pintype "passive"))
    )
    (net (code "14") (name "/LLC_IN_3") (class "Default")
      (node (ref "R50") (pin "1") (pinfunction "1_1") (pintype "passive"))
    )
    (net (code "15") (name "/OUT_B1") (class "Default")
      (node (ref "R13") (pin "1") (pinfunction "1_1") (pintype "passive"))
      (node (ref "R22") (pin "2") (pinfunction "2_2") (pintype "passive"))
      (node (ref "R9") (pin "2") (pinfunction "2_2") (pintype "passive"))
      (node (ref "U4") (pin "7") (pinfunction "OUT_B_7") (pintype "output"))
    )
    (net (code "16") (name "/OUT_B2") (class "Default")
      (node (ref "R25") (pin "2") (pinfunction "2_2") (pintype "passive"))
      (node (ref "R29") (pin "1") (pinfunction "1_1") (pintype "passive"))
      (node (ref "R38") (pin "2") (pinfunction "2_2") (pintype "passive"))
      (node (ref "U6") (pin "7") (pinfunction "OUT_B_7") (pintype "output"))
    )
    (net (code "17") (name "/OUT_B3") (class "Default")
      (node (ref "R41") (pin "2") (pinfunction "2_2") (pintype "passive"))
      (node (ref "R45") (pin "1") (pinfunction "1_1") (pintype "passive"))
      (node (ref "R54") (pin "2") (pinfunction "2_2") (pintype "passive"))
      (node (ref "U8") (pin "7") (pinfunction "OUT_B_7") (pintype "output"))
    )
    (net (code "18") (name "GND") (class "Default")
      (node (ref "C21") (pin "1") (pinfunction "1_1") (pintype "passive"))
      (node (ref "C22") (pin "1") (pinfunction "1_1") (pintype "passive"))
      (node (ref "C23") (pin "1") (pinfunction "1_1") (pintype "passive"))
      (node (ref "C27") (pin "1") (pinfunction "1_1") (pintype "passive"))
      (node (ref "C28") (pin "1") (pinfunction "1_1") (pintype "passive"))
      (node (ref "C29") (pin "1") (pinfunction "1_1") (pintype "passive"))
      (node (ref "C33") (pin "1") (pinfunction "1_1") (pintype "passive"))
      (node (ref "C34") (pin "1") (pinfunction "1_1") (pintype "passive"))
      (node (ref "C35") (pin "1") (pinfunction "1_1") (pintype "passive"))
      (node (ref "R15") (pin "1") (pinfunction "1_1") (pintype "passive"))
      (node (ref "R16") (pin "1") (pinfunction "1_1") (pintype "passive"))
      (node (ref "R17") (pin "1") (pinfunction "1_1") (pintype "passive"))
      (node (ref "R19") (pin "1") (pinfunction "1_1") (pintype "passive"))
      (node (ref "R21") (pin "1") (pinfunction "1_1") (pintype "passive"))
      (node (ref "R23") (pin "1") (pinfunction "1_1") (pintype "passive"))
      (node (ref "R31") (pin "1") (pinfunction "1_1") (pintype "passive"))
      (node (ref "R32") (pin "1") (pinfunction "1_1") (pintype "passive"))
      (node (ref "R33") (pin "1") (pinfunction "1_1") (pintype "passive"))
      (node (ref "R35") (pin "1") (pinfunction "1_1") (pintype "passive"))
      (node (ref "R37") (pin "1") (pinfunction "1_1") (pintype "passive"))
      (node (ref "R39") (pin "1") (pinfunction "1_1") (pintype "passive"))
      (node (ref "R47") (pin "1") (pinfunction "1_1") (pintype "passive"))
      (node (ref "R48") (pin "1") (pinfunction "1_1") (pintype "passive"))
      (node (ref "R49") (pin "1") (pinfunction "1_1") (pintype "passive"))
      (node (ref "R51") (pin "1") (pinfunction "1_1") (pintype "passive"))
      (node (ref "R53") (pin "1") (pinfunction "1_1") (pintype "passive"))
      (node (ref "R55") (pin "1") (pinfunction "1_1") (pintype "passive"))
    )
    (net (code "19") (name "Net-(C18-Pad1)") (class "Default")
      (node (ref "C18") (pin "1") (pinfunction "1_1") (pintype "passive"))
      (node (ref "C23") (pin "2") (pinfunction "2_2") (pintype "passive"))
      (node (ref "R14") (pin "2") (pinfunction "2_2") (pintype "passive"))
      (node (ref "R9") (pin "1") (pinfunction "1_1") (pintype "passive"))
    )
    (net (code "20") (name "Net-(C19-Pad2)") (class "Default")
      (node (ref "C19") (pin "2") (pinfunction "2_2") (pintype "passive"))
      (node (ref "C22") (pin "2") (pinfunction "2_2") (pintype "passive"))
      (node (ref "R10") (pin "1") (pinfunction "1_1") (pintype "passive"))
      (node (ref "R13") (pin "2") (pinfunction "2_2") (pintype "passive"))
    )
    (net (code "21") (name "Net-(C20-Pad1)") (class "Default")
      (node (ref "C20") (pin "1") (pinfunction "1_1") (pintype "passive"))
      (node (ref "C21") (pin "2") (pinfunction "2_2") (pintype "passive"))
      (node (ref "R11") (pin "1") (pinfunction "1_1") (pintype "passive"))
      (node (ref "R12") (pin "2") (pinfunction "2_2") (pintype "passive"))
    )
    (net (code "22") (name "Net-(C24-Pad1)") (class "Default")
      (node (ref "C24") (pin "1") (pinfunction "1_1") (pintype "passive"))
      (node (ref "C29") (pin "2") (pinfunction "2_2") (pintype "passive"))
      (node (ref "R25") (pin "1") (pinfunction "1_1") (pintype "passive"))
      (node (ref "R30") (pin "2") (pinfunction "2_2") (pintype "passive"))
    )
    (net (code "23") (name "Net-(C25-Pad2)") (class "Default")
      (node (ref "C25") (pin "2") (pinfunction "2_2") (pintype "passive"))
      (node (ref "C28") (pin "2") (pinfunction "2_2") (pintype "passive"))
      (node (ref "R26") (pin "1") (pinfunction "1_1") (pintype "passive"))
      (node (ref "R29") (pin "2") (pinfunction "2_2") (pintype "passive"))
    )
    (net (code "24") (name "Net-(C26-Pad1)") (class "Default")
      (node (ref "C26") (pin "1") (pinfunction "1_1") (pintype "passive"))
      (node (ref "C27") (pin "2") (pinfunction "2_2") (pintype "passive"))
      (node (ref "R27") (pin "1") (pinfunction "1_1") (pintype "passive"))
      (node (ref "R28") (pin "2") (pinfunction "2_2") (pintype "passive"))
    )
    (net (code "25") (name "Net-(C30-Pad1)") (class "Default")
      (node (ref "C30") (pin "1") (pinfunction "1_1") (pintype "passive"))
      (node (ref "C35") (pin "2") (pinfunction "2_2") (pintype "passive"))
      (node (ref "R41") (pin "1") (pinfunction "1_1") (pintype "passive"))
      (node (ref "R46") (pin "2") (pinfunction "2_2") (pintype "passive"))
    )
    (net (code "26") (name "Net-(C31-Pad2)") (class "Default")
      (node (ref "C31") (pin "2") (pinfunction "2_2") (pintype "passive"))
      (node (ref "C34") (pin "2") (pinfunction "2_2") (pintype "passive"))
      (node (ref "R42") (pin "1") (pinfunction "1_1") (pintype "passive"))
      (node (ref "R45") (pin "2") (pinfunction "2_2") (pintype "passive"))
    )
    (net (code "27") (name "Net-(C32-Pad1)") (class "Default")
      (node (ref "C32") (pin "1") (pinfunction "1_1") (pintype "passive"))
      (node (ref "C33") (pin "2") (pinfunction "2_2") (pintype "passive"))
      (node (ref "R43") (pin "1") (pinfunction "1_1") (pintype "passive"))
      (node (ref "R44") (pin "2") (pinfunction "2_2") (pintype "passive"))
    )
    (net (code "28") (name "Net-(J4-SLEEVE)") (class "Default")
      (node (ref "J4") (pin "1") (pinfunction "SLEEVE_1") (pintype "passive"))
      (node (ref "R12") (pin "1") (pinfunction "1_1") (pintype "passive"))
      (node (ref "TP_SIGNAL_IN") (pin "1") (pinfunction "TP_1") (pintype "passive"))
    )
    (net (code "29") (name "Net-(J5-SLEEVE)") (class "Default")
      (node (ref "J5") (pin "1") (pinfunction "SLEEVE_1") (pintype "passive"))
      (node (ref "R28") (pin "1") (pinfunction "1_1") (pintype "passive"))
    )
    (net (code "30") (name "Net-(J6-SLEEVE)") (class "Default")
      (node (ref "J6") (pin "1") (pinfunction "SLEEVE_1") (pintype "passive"))
      (node (ref "R44") (pin "1") (pinfunction "1_1") (pintype "passive"))
    )
    (net (code "31") (name "Net-(U4-+INA)") (class "Default")
      (node (ref "C20") (pin "2") (pinfunction "2_2") (pintype "passive"))
      (node (ref "R15") (pin "2") (pinfunction "2_2") (pintype "passive"))
      (node (ref "U4") (pin "3") (pinfunction "+INA_3") (pintype "input"))
    )
    (net (code "32") (name "Net-(U4--INA)") (class "Default")
      (node (ref "R19") (pin "2") (pinfunction "2_2") (pintype "passive"))
      (node (ref "R20") (pin "1") (pinfunction "1_1") (pintype "passive"))
      (node (ref "U4") (pin "2") (pinfunction "-INA_2") (pintype "input"))
    )
    (net (code "33") (name "Net-(U4-OUT_A)") (class "Default")
      (node (ref "R11") (pin "2") (pinfunction "2_2") (pintype "passive"))
      (node (ref "R14") (pin "1") (pinfunction "1_1") (pintype "passive"))
      (node (ref "R20") (pin "2") (pinfunction "2_2") (pintype "passive"))
      (node (ref "U4") (pin "1") (pinfunction "OUT_A_1") (pintype "output"))
    )
    (net (code "34") (name "Net-(U5-+INA)") (class "Default")
      (node (ref "C19") (pin "1") (pinfunction "1_1") (pintype "passive"))
      (node (ref "R17") (pin "2") (pinfunction "2_2") (pintype "passive"))
      (node (ref "U5") (pin "3") (pinfunction "+INA_3") (pintype "input"))
    )
    (net (code "35") (name "Net-(U5--INA)") (class "Default")
      (node (ref "R23") (pin "2") (pinfunction "2_2") (pintype "passive"))
      (node (ref "R24") (pin "1") (pinfunction "1_1") (pintype "passive"))
      (node (ref "U5") (pin "2") (pinfunction "-INA_2") (pintype "input"))
    )
    (net (code "36") (name "Net-(U6-+INA)") (class "Default")
      (node (ref "C26") (pin "2") (pinfunction "2_2") (pintype "passive"))
      (node (ref "R31") (pin "2") (pinfunction "2_2") (pintype "passive"))
      (node (ref "U6") (pin "3") (pinfunction "+INA_3") (pintype "input"))
    )
    (net (code "37") (name "Net-(U6--INA)") (class "Default")
      (node (ref "R35") (pin "2") (pinfunction "2_2") (pintype "passive"))
      (node (ref "R36") (pin "1") (pinfunction "1_1") (pintype "passive"))
      (node (ref "U6") (pin "2") (pinfunction "-INA_2") (pintype "input"))
    )
    (net (code "38") (name "Net-(U6-OUT_A)") (class "Default")
      (node (ref "R27") (pin "2") (pinfunction "2_2") (pintype "passive"))
      (node (ref "R30") (pin "1") (pinfunction "1_1") (pintype "passive"))
      (node (ref "R36") (pin "2") (pinfunction "2_2") (pintype "passive"))
      (node (ref "U6") (pin "1") (pinfunction "OUT_A_1") (pintype "output"))
    )
    (net (code "39") (name "Net-(U7-+INA)") (class "Default")
      (node (ref "C25") (pin "1") (pinfunction "1_1") (pintype "passive"))
      (node (ref "R33") (pin "2") (pinfunction "2_2") (pintype "passive"))
      (node (ref "U7") (pin "3") (pinfunction "+INA_3") (pintype "input"))
    )
    (net (code "40") (name "Net-(U7--INA)") (class "Default")
      (node (ref "R39") (pin "2") (pinfunction "2_2") (pintype "passive"))
      (node (ref "R40") (pin "1") (pinfunction "1_1") (pintype "passive"))
      (node (ref "U7") (pin "2") (pinfunction "-INA_2") (pintype "input"))
    )
    (net (code "41") (name "Net-(U8-+INA)") (class "Default")
      (node (ref "C32") (pin "2") (pinfunction "2_2") (pintype "passive"))
      (node (ref "R47") (pin "2") (pinfunction "2_2") (pintype "passive"))
      (node (ref "U8") (pin "3") (pinfunction "+INA_3") (pintype "input"))
    )
    (net (code "42") (name "Net-(U8--INA)") (class "Default")
      (node (ref "R51") (pin "2") (pinfunction "2_2") (pintype "passive"))
      (node (ref "R52") (pin "1") (pinfunction "1_1") (pintype "passive"))
      (node (ref "U8") (pin "2") (pinfunction "-INA_2") (pintype "input"))
    )
    (net (code "43") (name "Net-(U8-OUT_A)") (class "Default")
      (node (ref "R43") (pin "2") (pinfunction "2_2") (pintype "passive"))
      (node (ref "R46") (pin "1") (pinfunction "1_1") (pintype "passive"))
      (node (ref "R52") (pin "2") (pinfunction "2_2") (pintype "passive"))
      (node (ref "U8") (pin "1") (pinfunction "OUT_A_1") (pintype "output"))
    )
    (net (code "44") (name "Net-(U9-+INA)") (class "Default")
      (node (ref "C31") (pin "1") (pinfunction "1_1") (pintype "passive"))
      (node (ref "R49") (pin "2") (pinfunction "2_2") (pintype "passive"))
      (node (ref "U9") (pin "3") (pinfunction "+INA_3") (pintype "input"))
    )
    (net (code "45") (name "Net-(U9--INA)") (class "Default")
      (node (ref "R55") (pin "2") (pinfunction "2_2") (pintype "passive"))
      (node (ref "R56") (pin "1") (pinfunction "1_1") (pintype "passive"))
      (node (ref "U9") (pin "2") (pinfunction "-INA_2") (pintype "input"))
    )
    (net (code "46") (name "unconnected-(J4-TIP-Pad2)") (class "Default")
      (node (ref "J4") (pin "2") (pinfunction "TIP_2") (pintype "passive+no_connect"))
    )
    (net (code "47") (name "unconnected-(J4-TIP_SWITCH-Pad4)") (class "Default")
      (node (ref "J4") (pin "4") (pinfunction "TIP_SWITCH_4") (pintype "passive+no_connect"))
    )
    (net (code "48") (name "unconnected-(J5-TIP-Pad2)") (class "Default")
      (node (ref "J5") (pin "2") (pinfunction "TIP_2") (pintype "passive+no_connect"))
    )
    (net (code "49") (name "unconnected-(J5-TIP_SWITCH-Pad4)") (class "Default")
      (node (ref "J5") (pin "4") (pinfunction "TIP_SWITCH_4") (pintype "passive+no_connect"))
    )
    (net (code "50") (name "unconnected-(J6-TIP-Pad2)") (class "Default")
      (node (ref "J6") (pin "2") (pinfunction "TIP_2") (pintype "passive+no_connect"))
    )
    (net (code "51") (name "unconnected-(J6-TIP_SWITCH-Pad4)") (class "Default")
      (node (ref "J6") (pin "4") (pinfunction "TIP_SWITCH_4") (pintype "passive+no_connect"))
    )
    (net (code "52") (name "unconnected-(U5-+INB-Pad5)") (class "Default")
      (node (ref "U5") (pin "5") (pinfunction "+INB_5") (pintype "input+no_connect"))
    )
    (net (code "53") (name "unconnected-(U5--INB-Pad6)") (class "Default")
      (node (ref "U5") (pin "6") (pinfunction "-INB_6") (pintype "input+no_connect"))
    )
    (net (code "54") (name "unconnected-(U5-OUT_B-Pad7)") (class "Default")
      (node (ref "U5") (pin "7") (pinfunction "OUT_B_7") (pintype "output+no_connect"))
    )
    (net (code "55") (name "unconnected-(U7-+INB-Pad5)") (class "Default")
      (node (ref "U7") (pin "5") (pinfunction "+INB_5") (pintype "input+no_connect"))
    )
    (net (code "56") (name "unconnected-(U7--INB-Pad6)") (class "Default")
      (node (ref "U7") (pin "6") (pinfunction "-INB_6") (pintype "input+no_connect"))
    )
    (net (code "57") (name "unconnected-(U7-OUT_B-Pad7)") (class "Default")
      (node (ref "U7") (pin "7") (pinfunction "OUT_B_7") (pintype "output+no_connect"))
    )
    (net (code "58") (name "unconnected-(U9-+INB-Pad5)") (class "Default")
      (node (ref "U9") (pin "5") (pinfunction "+INB_5") (pintype "input+no_connect"))
    )
    (net (code "59") (name "unconnected-(U9--INB-Pad6)") (class "Default")
      (node (ref "U9") (pin "6") (pinfunction "-INB_6") (pintype "input+no_connect"))
    )
    (net (code "60") (name "unconnected-(U9-OUT_B-Pad7)") (class "Default")
      (node (ref "U9") (pin "7") (pinfunction "OUT_B_7") (pintype "output+no_connect"))
    )
  )
)
